# breakout_da14580.net
KiCad netlist of a schematic drawn in EAGLE
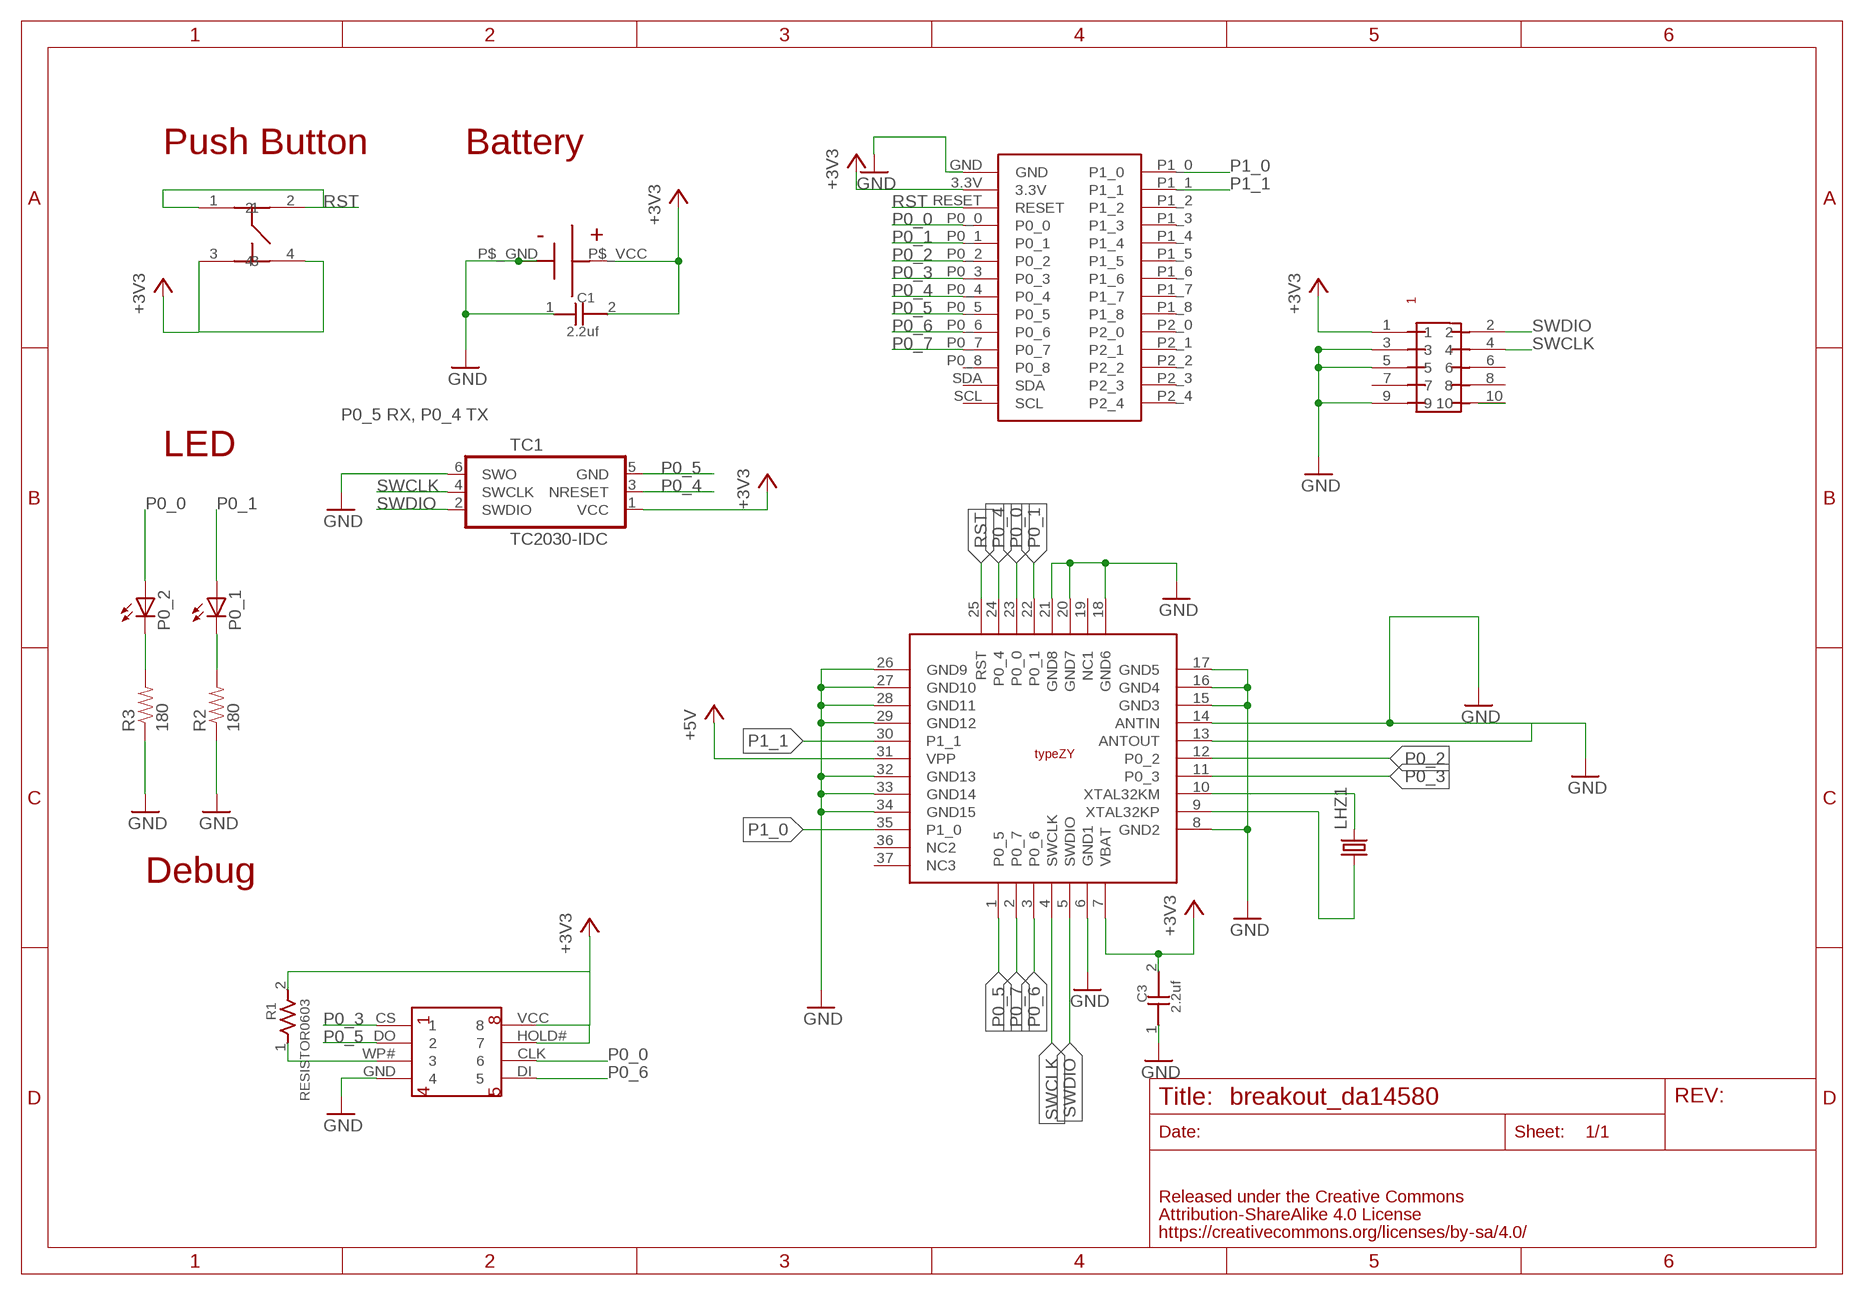
[diagram p0: schematic, sheet 1]

(export (version "E")
  (design (tool "Eeschema 10.0.6"))
  (components
    (comp (ref "C1")
      (value "2.2uf")
      (footprint "eagle-import:0603")
      (libsource (lib "eagle-import") (part "CAPACITOR0603"))
    )
    (comp (ref "C3")
      (value "2.2uf")
      (footprint "eagle-import:0603")
      (libsource (lib "eagle-import") (part "CAPACITOR0603"))
    )
    (comp (ref "LHZ1")
      (value "FC-12M")
      (footprint "eagle-import:FC-12M")
      (libsource (lib "eagle-import") (part "FC-12M"))
    )
    (comp (ref "P0_1")
      (value "LEDCHIP-LED0603")
      (footprint "eagle-import:CHIP-LED0603")
      (libsource (lib "eagle-import") (part "LEDCHIP-LED0603"))
    )
    (comp (ref "P0_2")
      (value "LEDCHIP-LED0603")
      (footprint "eagle-import:CHIP-LED0603")
      (libsource (lib "eagle-import") (part "LEDCHIP-LED0603"))
    )
    (comp (ref "R1")
      (value "RESISTOR0603")
      (footprint "eagle-import:0603")
      (libsource (lib "eagle-import") (part "RESISTOR0603"))
    )
    (comp (ref "R2")
      (value "180")
      (footprint "eagle-import:0603-RES")
      (libsource (lib "eagle-import") (part "RESISTOR0603-RES"))
    )
    (comp (ref "R3")
      (value "180")
      (footprint "eagle-import:0603-RES")
      (libsource (lib "eagle-import") (part "RESISTOR0603-RES"))
    )
    (comp (ref "TC1")
      (value "TC2030-IDC")
      (footprint "eagle-import:TC2030-IDC")
      (libsource (lib "eagle-import") (part "TC2030-IDC"))
    )
    (comp (ref "U$1")
      (value "MURATA-TYPEZY")
      (footprint "eagle-import:MURATA_TYPEZY")
      (libsource (lib "eagle-import") (part "MURATA-TYPEZY"))
    )
    (comp (ref "U$2")
      (value "BREAKOUT_BLE")
      (footprint "eagle-import:BREAKOUT_BLE")
      (libsource (lib "eagle-import") (part "BREAKOUT_BLE"))
    )
    (comp (ref "U$3")
      (value "SMTU2450-TOP")
      (footprint "eagle-import:SMTU2450")
      (libsource (lib "eagle-import") (part "SMTU2450-TOP"))
    )
    (comp (ref "U$5")
      (value "FLASH-MEMORY-2M(WINBOND)")
      (footprint "eagle-import:FLASH-MEMORY-2M(WINBOND)")
      (libsource (lib "eagle-import") (part "FLASH-MEMORY-2M(WINBOND)"))
    )
    (comp (ref "U$6")
      (value "PIN-HEADER-SMT(1.27MM)2X5")
      (footprint "eagle-import:PIN-HEADER-SMT(1.27MM)2X5")
      (libsource (lib "eagle-import") (part "PIN-HEADER-SMT(1.27MM)2X5"))
    )
    (comp (ref "U$7")
      (value "SWICTH-4P(KMR2)")
      (footprint "eagle-import:SWITCH-4P(KMR2)")
      (libsource (lib "eagle-import") (part "SWICTH-4P(KMR2)"))
    )
  )
  (nets
    (net (code "1") (name "+3V3") (class "Default")
      (node (ref "C1") (pin "2") (pinfunction "2_2") (pintype "passive"))
      (node (ref "C3") (pin "2") (pinfunction "2_2") (pintype "passive"))
      (node (ref "R1") (pin "2") (pinfunction "2_2") (pintype "passive"))
      (node (ref "TC1") (pin "1") (pinfunction "VCC_1") (pintype "passive"))
      (node (ref "U$1") (pin "7") (pinfunction "VBAT_7") (pintype "bidirectional"))
      (node (ref "U$2") (pin "3.3V") (pinfunction "3.3V_3.3V") (pintype "bidirectional"))
      (node (ref "U$3") (pin "P$_VCC") (pinfunction "+_P$_VCC") (pintype "bidirectional"))
      (node (ref "U$5") (pin "HOLD#") (pinfunction "7_HOLD#") (pintype "bidirectional"))
      (node (ref "U$5") (pin "VCC") (pinfunction "8_VCC") (pintype "bidirectional"))
      (node (ref "U$6") (pin "1") (pinfunction "1_1") (pintype "bidirectional"))
      (node (ref "U$7") (pin "3") (pinfunction "3_3") (pintype "bidirectional"))
      (node (ref "U$7") (pin "4") (pinfunction "4_4") (pintype "bidirectional"))
    )
    (net (code "2") (name "+5V") (class "Default")
      (node (ref "U$1") (pin "31") (pinfunction "VPP_31") (pintype "bidirectional"))
    )
    (net (code "3") (name "GND") (class "Default")
      (node (ref "C1") (pin "1") (pinfunction "1_1") (pintype "passive"))
      (node (ref "C3") (pin "1") (pinfunction "1_1") (pintype "passive"))
      (node (ref "R2") (pin "1") (pinfunction "1_1") (pintype "passive"))
      (node (ref "R3") (pin "1") (pinfunction "1_1") (pintype "passive"))
      (node (ref "TC1") (pin "6") (pinfunction "SWO_6") (pintype "passive"))
      (node (ref "U$1") (pin "14") (pinfunction "ANTIN_14") (pintype "bidirectional"))
      (node (ref "U$1") (pin "15") (pinfunction "GND3_15") (pintype "bidirectional"))
      (node (ref "U$1") (pin "16") (pinfunction "GND4_16") (pintype "bidirectional"))
      (node (ref "U$1") (pin "17") (pinfunction "GND5_17") (pintype "bidirectional"))
      (node (ref "U$1") (pin "18") (pinfunction "GND6_18") (pintype "bidirectional"))
      (node (ref "U$1") (pin "20") (pinfunction "GND7_20") (pintype "bidirectional"))
      (node (ref "U$1") (pin "21") (pinfunction "GND8_21") (pintype "bidirectional"))
      (node (ref "U$1") (pin "26") (pinfunction "GND9_26") (pintype "bidirectional"))
      (node (ref "U$1") (pin "27") (pinfunction "GND10_27") (pintype "bidirectional"))
      (node (ref "U$1") (pin "28") (pinfunction "GND11_28") (pintype "bidirectional"))
      (node (ref "U$1") (pin "29") (pinfunction "GND12_29") (pintype "bidirectional"))
      (node (ref "U$1") (pin "32") (pinfunction "GND13_32") (pintype "bidirectional"))
      (node (ref "U$1") (pin "33") (pinfunction "GND14_33") (pintype "bidirectional"))
      (node (ref "U$1") (pin "34") (pinfunction "GND15_34") (pintype "bidirectional"))
      (node (ref "U$1") (pin "6") (pinfunction "GND1_6") (pintype "bidirectional"))
      (node (ref "U$1") (pin "8") (pinfunction "GND2_8") (pintype "bidirectional"))
      (node (ref "U$2") (pin "GND") (pinfunction "GND_GND") (pintype "bidirectional"))
      (node (ref "U$3") (pin "P$_GND") (pinfunction "-_P$_GND") (pintype "bidirectional"))
      (node (ref "U$5") (pin "GND") (pinfunction "4_GND") (pintype "bidirectional"))
      (node (ref "U$6") (pin "3") (pinfunction "3_3") (pintype "bidirectional"))
      (node (ref "U$6") (pin "5") (pinfunction "5_5") (pintype "bidirectional"))
      (node (ref "U$6") (pin "9") (pinfunction "9_9") (pintype "bidirectional"))
    )
    (net (code "4") (name "Net-(P0_1-PadC)") (class "Default")
      (node (ref "P0_1") (pin "C") (pinfunction "C_C") (pintype "passive"))
      (node (ref "R2") (pin "2") (pinfunction "2_2") (pintype "passive"))
    )
    (net (code "5") (name "Net-(P0_2-PadC)") (class "Default")
      (node (ref "P0_2") (pin "C") (pinfunction "C_C") (pintype "passive"))
      (node (ref "R3") (pin "2") (pinfunction "2_2") (pintype "passive"))
    )
    (net (code "6") (name "Net-(U$1-XTAL32KM)") (class "Default")
      (node (ref "LHZ1") (pin "2") (pinfunction "2_2") (pintype "passive"))
      (node (ref "U$1") (pin "10") (pinfunction "XTAL32KM_10") (pintype "bidirectional"))
    )
    (net (code "7") (name "Net-(U$1-XTAL32KP)") (class "Default")
      (node (ref "LHZ1") (pin "1") (pinfunction "1_1") (pintype "passive"))
      (node (ref "U$1") (pin "9") (pinfunction "XTAL32KP_9") (pintype "bidirectional"))
    )
    (net (code "8") (name "Net-(U$5-3)") (class "Default")
      (node (ref "R1") (pin "1") (pinfunction "1_1") (pintype "passive"))
      (node (ref "U$5") (pin "WP#") (pinfunction "3_WP#") (pintype "bidirectional"))
    )
    (net (code "9") (name "P0_0") (class "Default")
      (node (ref "P0_2") (pin "A") (pinfunction "A_A") (pintype "passive"))
      (node (ref "U$1") (pin "23") (pinfunction "P0_0_23") (pintype "bidirectional"))
      (node (ref "U$2") (pin "P0_0") (pinfunction "P0_0_P0_0") (pintype "bidirectional"))
      (node (ref "U$5") (pin "CLK") (pinfunction "6_CLK") (pintype "bidirectional"))
    )
    (net (code "10") (name "P0_1") (class "Default")
      (node (ref "P0_1") (pin "A") (pinfunction "A_A") (pintype "passive"))
      (node (ref "U$1") (pin "22") (pinfunction "P0_1_22") (pintype "bidirectional"))
      (node (ref "U$2") (pin "P0_1") (pinfunction "P0_1_P0_1") (pintype "bidirectional"))
    )
    (net (code "11") (name "P0_2") (class "Default")
      (node (ref "U$1") (pin "12") (pinfunction "P0_2_12") (pintype "bidirectional"))
      (node (ref "U$2") (pin "P0_2") (pinfunction "P0_2_P0_2") (pintype "bidirectional"))
    )
    (net (code "12") (name "P0_3") (class "Default")
      (node (ref "U$1") (pin "11") (pinfunction "P0_3_11") (pintype "bidirectional"))
      (node (ref "U$2") (pin "P0_3") (pinfunction "P0_3_P0_3") (pintype "bidirectional"))
      (node (ref "U$5") (pin "CS") (pinfunction "1_CS") (pintype "bidirectional"))
    )
    (net (code "13") (name "P0_4") (class "Default")
      (node (ref "TC1") (pin "3") (pinfunction "NRESET_3") (pintype "passive"))
      (node (ref "U$1") (pin "24") (pinfunction "P0_4_24") (pintype "bidirectional"))
      (node (ref "U$2") (pin "P0_4") (pinfunction "P0_4_P0_4") (pintype "bidirectional"))
    )
    (net (code "14") (name "P0_5") (class "Default")
      (node (ref "TC1") (pin "5") (pinfunction "GND_5") (pintype "passive"))
      (node (ref "U$1") (pin "1") (pinfunction "P0_5_1") (pintype "bidirectional"))
      (node (ref "U$2") (pin "P0_5") (pinfunction "P0_5_P0_5") (pintype "bidirectional"))
      (node (ref "U$5") (pin "DO") (pinfunction "2_DO") (pintype "bidirectional"))
    )
    (net (code "15") (name "P0_6") (class "Default")
      (node (ref "U$1") (pin "3") (pinfunction "P0_6_3") (pintype "bidirectional"))
      (node (ref "U$2") (pin "P0_6") (pinfunction "P0_6_P0_6") (pintype "bidirectional"))
      (node (ref "U$5") (pin "DI") (pinfunction "5_DI") (pintype "bidirectional"))
    )
    (net (code "16") (name "P0_7") (class "Default")
      (node (ref "U$1") (pin "2") (pinfunction "P0_7_2") (pintype "bidirectional"))
      (node (ref "U$2") (pin "P0_7") (pinfunction "P0_7_P0_7") (pintype "bidirectional"))
    )
    (net (code "17") (name "P1_0") (class "Default")
      (node (ref "U$1") (pin "35") (pinfunction "P1_0_35") (pintype "bidirectional"))
      (node (ref "U$2") (pin "P1_0") (pinfunction "P1_0_P1_0") (pintype "bidirectional"))
    )
    (net (code "18") (name "P1_1") (class "Default")
      (node (ref "U$1") (pin "30") (pinfunction "P1_1_30") (pintype "bidirectional"))
      (node (ref "U$2") (pin "P1_1") (pinfunction "P1_1_P1_1") (pintype "bidirectional"))
    )
    (net (code "19") (name "RST") (class "Default")
      (node (ref "U$1") (pin "25") (pinfunction "RST_25") (pintype "bidirectional"))
      (node (ref "U$2") (pin "RESET") (pinfunction "RESET_RESET") (pintype "bidirectional"))
      (node (ref "U$7") (pin "1") (pinfunction "1_1") (pintype "bidirectional"))
      (node (ref "U$7") (pin "2") (pinfunction "2_2") (pintype "bidirectional"))
    )
    (net (code "20") (name "SWCLK") (class "Default")
      (node (ref "TC1") (pin "4") (pinfunction "SWCLK_4") (pintype "passive"))
      (node (ref "U$1") (pin "4") (pinfunction "SWCLK_4") (pintype "bidirectional"))
      (node (ref "U$6") (pin "4") (pinfunction "4_4") (pintype "bidirectional"))
    )
    (net (code "21") (name "SWDIO") (class "Default")
      (node (ref "TC1") (pin "2") (pinfunction "SWDIO_2") (pintype "passive"))
      (node (ref "U$1") (pin "5") (pinfunction "SWDIO_5") (pintype "bidirectional"))
      (node (ref "U$6") (pin "2") (pinfunction "2_2") (pintype "bidirectional"))
    )
    (net (code "22") (name "unconnected-(U$1-ANTOUT-Pad13)") (class "Default")
      (node (ref "U$1") (pin "13") (pinfunction "ANTOUT_13") (pintype "bidirectional"))
    )
    (net (code "23") (name "unconnected-(U$1-NC1-Pad19)") (class "Default")
      (node (ref "U$1") (pin "19") (pinfunction "NC1_19") (pintype "bidirectional"))
    )
    (net (code "24") (name "unconnected-(U$1-NC2-Pad36)") (class "Default")
      (node (ref "U$1") (pin "36") (pinfunction "NC2_36") (pintype "bidirectional"))
    )
    (net (code "25") (name "unconnected-(U$1-NC3-Pad37)") (class "Default")
      (node (ref "U$1") (pin "37") (pinfunction "NC3_37") (pintype "bidirectional"))
    )
    (net (code "26") (name "unconnected-(U$2-PadP0_8)") (class "Default")
      (node (ref "U$2") (pin "P0_8") (pinfunction "P0_8_P0_8") (pintype "bidirectional"))
    )
    (net (code "27") (name "unconnected-(U$2-PadP1_2)") (class "Default")
      (node (ref "U$2") (pin "P1_2") (pinfunction "P1_2_P1_2") (pintype "bidirectional"))
    )
    (net (code "28") (name "unconnected-(U$2-PadP1_3)") (class "Default")
      (node (ref "U$2") (pin "P1_3") (pinfunction "P1_3_P1_3") (pintype "bidirectional"))
    )
    (net (code "29") (name "unconnected-(U$2-PadP1_4)") (class "Default")
      (node (ref "U$2") (pin "P1_4") (pinfunction "P1_4_P1_4") (pintype "bidirectional"))
    )
    (net (code "30") (name "unconnected-(U$2-PadP1_5)") (class "Default")
      (node (ref "U$2") (pin "P1_5") (pinfunction "P1_5_P1_5") (pintype "bidirectional"))
    )
    (net (code "31") (name "unconnected-(U$2-PadP1_6)") (class "Default")
      (node (ref "U$2") (pin "P1_6") (pinfunction "P1_6_P1_6") (pintype "bidirectional"))
    )
    (net (code "32") (name "unconnected-(U$2-PadP1_7)") (class "Default")
      (node (ref "U$2") (pin "P1_7") (pinfunction "P1_7_P1_7") (pintype "bidirectional"))
    )
    (net (code "33") (name "unconnected-(U$2-PadP1_8)") (class "Default")
      (node (ref "U$2") (pin "P1_8") (pinfunction "P1_8_P1_8") (pintype "bidirectional"))
    )
    (net (code "34") (name "unconnected-(U$2-PadP2_0)") (class "Default")
      (node (ref "U$2") (pin "P2_0") (pinfunction "P2_0_P2_0") (pintype "bidirectional"))
    )
    (net (code "35") (name "unconnected-(U$2-PadP2_1)") (class "Default")
      (node (ref "U$2") (pin "P2_1") (pinfunction "P2_1_P2_1") (pintype "bidirectional"))
    )
    (net (code "36") (name "unconnected-(U$2-PadP2_2)") (class "Default")
      (node (ref "U$2") (pin "P2_2") (pinfunction "P2_2_P2_2") (pintype "bidirectional"))
    )
    (net (code "37") (name "unconnected-(U$2-PadP2_3)") (class "Default")
      (node (ref "U$2") (pin "P2_3") (pinfunction "P2_3_P2_3") (pintype "bidirectional"))
    )
    (net (code "38") (name "unconnected-(U$2-PadP2_4)") (class "Default")
      (node (ref "U$2") (pin "P2_4") (pinfunction "P2_4_P2_4") (pintype "bidirectional"))
    )
    (net (code "39") (name "unconnected-(U$2-PadSCL)") (class "Default")
      (node (ref "U$2") (pin "SCL") (pinfunction "SCL_SCL") (pintype "bidirectional"))
    )
    (net (code "40") (name "unconnected-(U$2-PadSDA)") (class "Default")
      (node (ref "U$2") (pin "SDA") (pinfunction "SDA_SDA") (pintype "bidirectional"))
    )
    (net (code "41") (name "unconnected-(U$6-Pad6)") (class "Default")
      (node (ref "U$6") (pin "6") (pinfunction "6_6") (pintype "bidirectional"))
    )
    (net (code "42") (name "unconnected-(U$6-Pad7)") (class "Default")
      (node (ref "U$6") (pin "7") (pinfunction "7_7") (pintype "bidirectional"))
    )
    (net (code "43") (name "unconnected-(U$6-Pad8)") (class "Default")
      (node (ref "U$6") (pin "8") (pinfunction "8_8") (pintype "bidirectional"))
    )
    (net (code "44") (name "unconnected-(U$6-Pad10)") (class "Default")
      (node (ref "U$6") (pin "10") (pinfunction "10_10") (pintype "bidirectional"))
    )
  )
)
